# Sheet1.net
KiCad netlist of a schematic drawn in Altium Designer
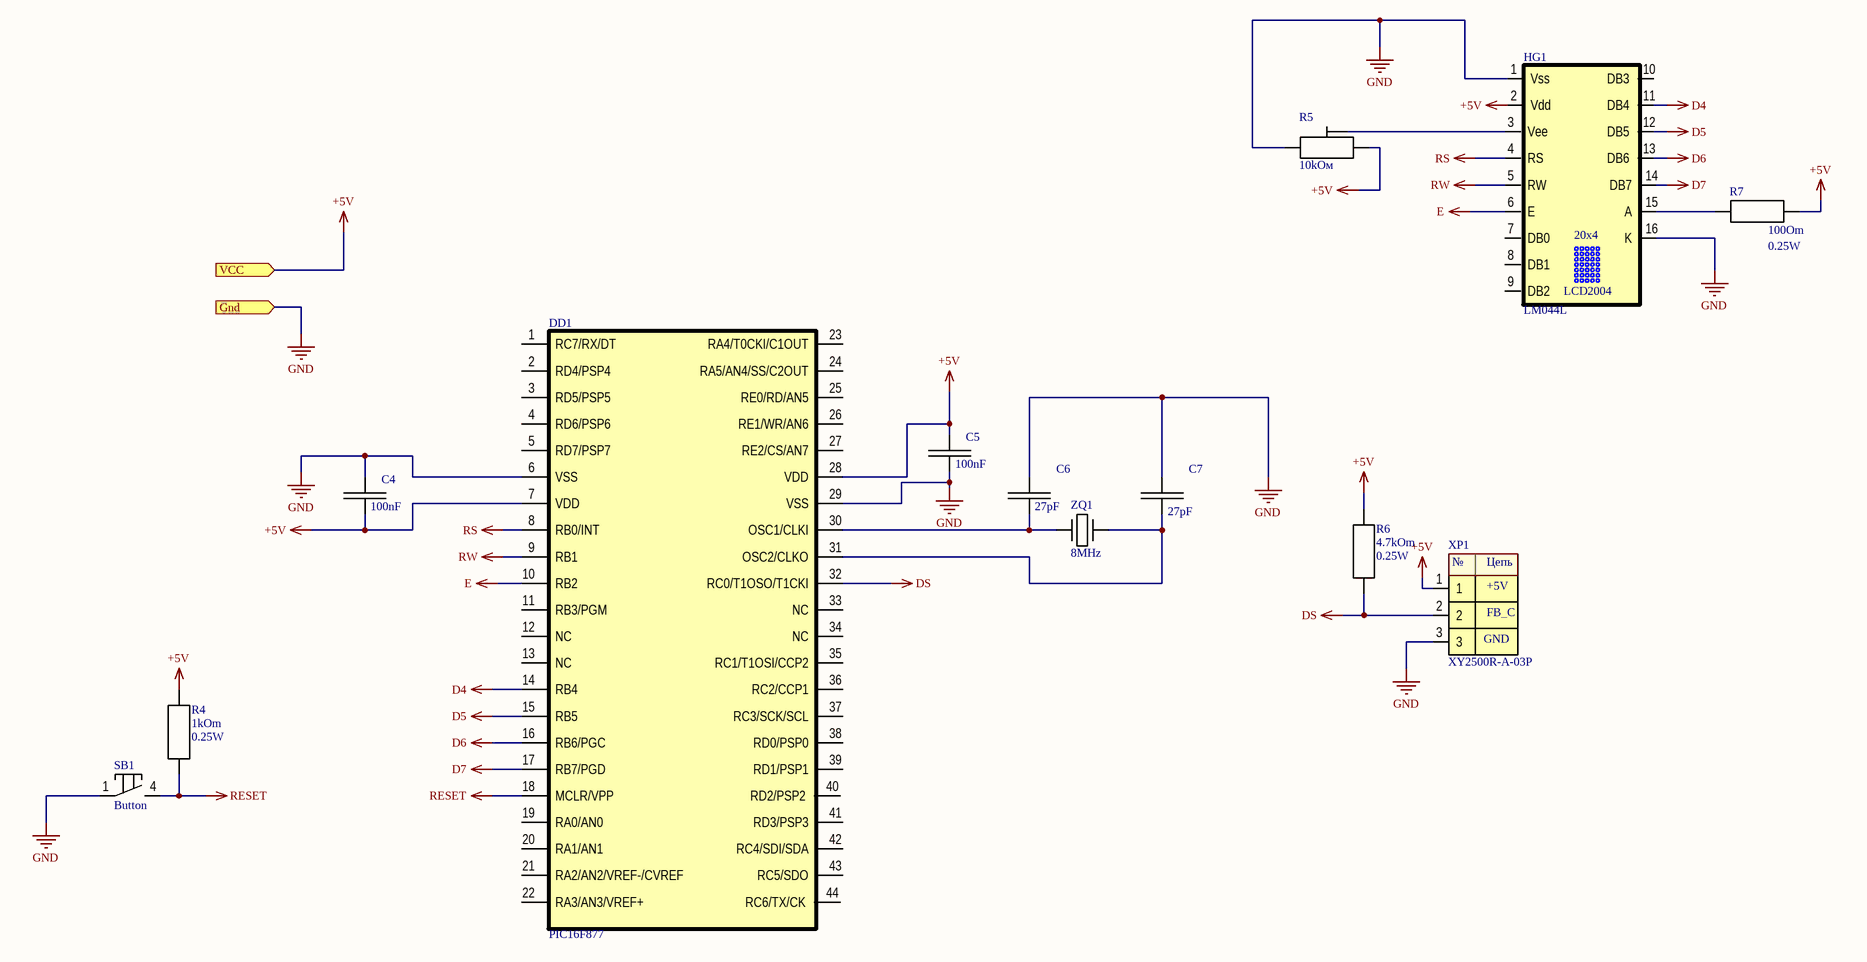
[diagram p0: Sheet1.SchDoc]

(export (version "E")
  (design (tool "Eeschema 10.0.6"))
  (components
    (comp (ref "C4")
      (value "100nF")
      (footprint "CAP1206")
      (fields
        (field (name "VOLTAGE") "100V")
        (field (name "PART NUMBER") "CL31B104KCFNNNE")
        (field (name "MANUFACTURER") "Samsung")
      )
      (libsource (lib "SchlibUGO") (part "Capasitor"))
    )
    (comp (ref "C5")
      (value "100nF")
      (footprint "CAP1206")
      (fields
        (field (name "VOLTAGE") "100V")
        (field (name "PART NUMBER") "CL31B104KCFNNNE")
        (field (name "MANUFACTURER") "Samsung")
      )
      (libsource (lib "SchlibUGO") (part "Capasitor"))
    )
    (comp (ref "C6")
      (value "27pF")
      (footprint "CAP1206")
      (fields
        (field (name "VOLTAGE") "50V")
        (field (name "PART NUMBER") "LFL106270NPO")
        (field (name "MANUFACTURER") "FAITHFULL LINK")
      )
      (libsource (lib "SchlibUGO") (part "Capasitor"))
    )
    (comp (ref "C7")
      (value "27pF")
      (footprint "CAP1206")
      (fields
        (field (name "VOLTAGE") "50V")
        (field (name "PART NUMBER") "FL1206270NPO")
        (field (name "MANUFACTURER") "FAITHFULL LINK")
      )
      (libsource (lib "SchlibUGO") (part "Capasitor"))
    )
    (comp (ref "DD1")
      (value "PIC16F877")
      (footprint "TQFP80P1200X1200X120-44N")
      (fields (field (name "PART NUMBER") "PIC16F877A") (field (name "MANUFACTURER") "Micchip"))
      (libsource (lib "SchlibUGO") (part "PIC16F877"))
    )
    (comp (ref "HG1")
      (value "LM044L")
      (footprint "LCD2004")
      (fields (field (name "PART NUMBER") "LM044L-HD44780U") (field (name "MANUFACTURER") "HITACHI"))
      (libsource (lib "SchlibUGO") (part "LM044L"))
    )
    (comp (ref "R4")
      (value "1kOm")
      (footprint "1206")
      (fields
        (field (name "MANUFACTURER") "Royal Ohm")
        (field (name "PART NUMBER") "SMD1206-1K")
        (field (name "POWER") "0.25W")
        (field (name "Comment") "Resistor")
      )
      (libsource (lib "SchlibUGO") (part "Resistor"))
    )
    (comp (ref "R5")
      (value "10kОм")
      (footprint "3006P")
      (fields
        (field (name "PART NUMBER") "3006-103-Z-LF")
        (field (name "MANUFACTURER") "Bours")
        (field (name "POWER") "0,125W")
      )
      (libsource (lib "SchlibUGO") (part "POT"))
    )
    (comp (ref "R6")
      (value "4.7kOm")
      (footprint "1206")
      (fields
        (field (name "MANUFACTURER") "Royal Ohm")
        (field (name "PART NUMBER") "SMD1206-1K")
        (field (name "POWER") "0.25W")
      )
      (libsource (lib "SchlibUGO") (part "Resistor"))
    )
    (comp (ref "R7")
      (value "100Om")
      (footprint "1206")
      (fields
        (field (name "MANUFACTURER") "YAGEO")
        (field (name "PART NUMBER") "RC1206FR-07100RL")
        (field (name "POWER") "0.25W")
      )
      (libsource (lib "SchlibUGO") (part "Resistor"))
    )
    (comp (ref "SB1") (value "Button") (footprint "KLS2") (libsource (lib "SchlibUGO") (part "Button")))
    (comp (ref "XP1")
      (value "XY2500R-A-03P")
      (footprint "XY2500R-A-03P")
      (fields (field (name "MANUFACTURER") "RUICHI"))
      (libsource (lib "SchlibUGO") (part "XY2500R-A-03P"))
    )
    (comp (ref "ZQ1")
      (value "8MHz")
      (footprint "HC-51U")
      (fields (field (name "PART NUMBER") "HC-51") (field (name "MANUFACTURER") "CHina"))
      (libsource (lib "SchlibUGO") (part "Rzanator"))
    )
  )
  (nets
    (net (code "1") (name "+5V") (class "Default")
      (node (ref "C4") (pin "2") (pinfunction "2_2") (pintype "passive"))
      (node (ref "C5") (pin "1") (pinfunction "1_1") (pintype "passive"))
      (node (ref "DD1") (pin "28") (pinfunction "VDD_28") (pintype "passive"))
      (node (ref "DD1") (pin "7") (pinfunction "VDD_7") (pintype "passive"))
      (node (ref "HG1") (pin "2") (pinfunction "Vdd_2") (pintype "passive"))
      (node (ref "R4") (pin "2") (pinfunction "2_2") (pintype "passive"))
      (node (ref "R5") (pin "3") (pinfunction "3_3") (pintype "passive"))
      (node (ref "R6") (pin "2") (pinfunction "2_2") (pintype "passive"))
      (node (ref "R7") (pin "1") (pinfunction "1_1") (pintype "passive"))
      (node (ref "XP1") (pin "1") (pinfunction "1_1") (pintype "passive"))
    )
    (net (code "2") (name "D4") (class "Default")
      (node (ref "DD1") (pin "14") (pinfunction "RB4_14") (pintype "passive"))
      (node (ref "HG1") (pin "11") (pinfunction "DB4_11") (pintype "passive"))
    )
    (net (code "3") (name "D5") (class "Default")
      (node (ref "DD1") (pin "15") (pinfunction "RB5_15") (pintype "passive"))
      (node (ref "HG1") (pin "12") (pinfunction "DB5_12") (pintype "passive"))
    )
    (net (code "4") (name "D6") (class "Default")
      (node (ref "DD1") (pin "16") (pinfunction "RB6/PGC_16") (pintype "passive"))
      (node (ref "HG1") (pin "13") (pinfunction "DB6_13") (pintype "passive"))
    )
    (net (code "5") (name "D7") (class "Default")
      (node (ref "DD1") (pin "17") (pinfunction "RB7/PGD_17") (pintype "passive"))
      (node (ref "HG1") (pin "14") (pinfunction "DB7_14") (pintype "passive"))
    )
    (net (code "6") (name "DS") (class "Default")
      (node (ref "DD1") (pin "32") (pinfunction "RC0/T1OSO/T1CKI_32") (pintype "passive"))
      (node (ref "R6") (pin "1") (pinfunction "1_1") (pintype "passive"))
      (node (ref "XP1") (pin "2") (pinfunction "2_2") (pintype "passive"))
    )
    (net (code "7") (name "E") (class "Default")
      (node (ref "DD1") (pin "10") (pinfunction "RB2_10") (pintype "passive"))
      (node (ref "HG1") (pin "6") (pinfunction "E_6") (pintype "passive"))
    )
    (net (code "8") (name "GND") (class "Default")
      (node (ref "C4") (pin "1") (pinfunction "1_1") (pintype "passive"))
      (node (ref "C5") (pin "2") (pinfunction "2_2") (pintype "passive"))
      (node (ref "C6") (pin "1") (pinfunction "1_1") (pintype "passive"))
      (node (ref "C7") (pin "1") (pinfunction "1_1") (pintype "passive"))
      (node (ref "DD1") (pin "29") (pinfunction "VSS_29") (pintype "passive"))
      (node (ref "DD1") (pin "6") (pinfunction "VSS_6") (pintype "passive"))
      (node (ref "HG1") (pin "1") (pinfunction "Vss_1") (pintype "passive"))
      (node (ref "HG1") (pin "16") (pinfunction "K_16") (pintype "passive"))
      (node (ref "R5") (pin "1") (pinfunction "1_1") (pintype "passive"))
      (node (ref "SB1") (pin "1") (pinfunction "1_1") (pintype "passive"))
      (node (ref "XP1") (pin "3") (pinfunction "3_3") (pintype "passive"))
    )
    (net (code "9") (name "Net-(DD1-OSC1{slash}CLKI)") (class "Default")
      (node (ref "C6") (pin "2") (pinfunction "2_2") (pintype "passive"))
      (node (ref "DD1") (pin "30") (pinfunction "OSC1/CLKI_30") (pintype "passive"))
      (node (ref "ZQ1") (pin "1") (pinfunction "1_1") (pintype "passive"))
    )
    (net (code "10") (name "Net-(DD1-OSC2{slash}CLKO)") (class "Default")
      (node (ref "C7") (pin "2") (pinfunction "2_2") (pintype "passive"))
      (node (ref "DD1") (pin "31") (pinfunction "OSC2/CLKO_31") (pintype "passive"))
      (node (ref "ZQ1") (pin "2") (pinfunction "2_2") (pintype "passive"))
    )
    (net (code "11") (name "Net-(HG1-A)") (class "Default")
      (node (ref "HG1") (pin "15") (pinfunction "A_15") (pintype "passive"))
      (node (ref "R7") (pin "2") (pinfunction "2_2") (pintype "passive"))
    )
    (net (code "12") (name "Net-(HG1-Vee)") (class "Default")
      (node (ref "HG1") (pin "3") (pinfunction "Vee_3") (pintype "passive"))
      (node (ref "R5") (pin "2") (pinfunction "2_2") (pintype "passive"))
    )
    (net (code "13") (name "RESET") (class "Default")
      (node (ref "DD1") (pin "18") (pinfunction "MCLR/VPP_18") (pintype "passive"))
      (node (ref "R4") (pin "1") (pinfunction "1_1") (pintype "passive"))
      (node (ref "SB1") (pin "4") (pinfunction "4_4") (pintype "passive"))
    )
    (net (code "14") (name "RS") (class "Default")
      (node (ref "DD1") (pin "8") (pinfunction "RB0/INT_8") (pintype "passive"))
      (node (ref "HG1") (pin "4") (pinfunction "RS_4") (pintype "passive"))
    )
    (net (code "15") (name "RW") (class "Default")
      (node (ref "DD1") (pin "9") (pinfunction "RB1_9") (pintype "passive"))
      (node (ref "HG1") (pin "5") (pinfunction "RW_5") (pintype "passive"))
    )
    (net (code "16") (name "unconnected-(DD1-NC-Pad12)") (class "Default")
      (node (ref "DD1") (pin "12") (pinfunction "NC_12") (pintype "passive"))
    )
    (net (code "17") (name "unconnected-(DD1-NC-Pad13)") (class "Default")
      (node (ref "DD1") (pin "13") (pinfunction "NC_13") (pintype "passive"))
    )
    (net (code "18") (name "unconnected-(DD1-NC-Pad33)") (class "Default")
      (node (ref "DD1") (pin "33") (pinfunction "NC_33") (pintype "passive"))
    )
    (net (code "19") (name "unconnected-(DD1-NC-Pad34)") (class "Default")
      (node (ref "DD1") (pin "34") (pinfunction "NC_34") (pintype "passive"))
    )
    (net (code "20") (name "unconnected-(DD1-RA0{slash}AN0-Pad19)") (class "Default")
      (node (ref "DD1") (pin "19") (pinfunction "RA0/AN0_19") (pintype "passive"))
    )
    (net (code "21") (name "unconnected-(DD1-RA1{slash}AN1-Pad20)") (class "Default")
      (node (ref "DD1") (pin "20") (pinfunction "RA1/AN1_20") (pintype "passive"))
    )
    (net (code "22") (name "unconnected-(DD1-RA2{slash}AN2{slash}VREF-{slash}CVREF-Pad21)") (class "Default")
      (node (ref "DD1") (pin "21") (pinfunction "RA2/AN2/VREF-/CVREF_21") (pintype "passive"))
    )
    (net (code "23") (name "unconnected-(DD1-RA3{slash}AN3{slash}VREF+-Pad22)") (class "Default")
      (node (ref "DD1") (pin "22") (pinfunction "RA3/AN3/VREF+_22") (pintype "passive"))
    )
    (net (code "24") (name "unconnected-(DD1-RA4{slash}T0CKI{slash}C1OUT-Pad23)") (class "Default")
      (node (ref "DD1") (pin "23") (pinfunction "RA4/T0CKI/C1OUT_23") (pintype "passive"))
    )
    (net (code "25") (name "unconnected-(DD1-RA5{slash}AN4{slash}SS{slash}C2OUT-Pad24)") (class "Default")
      (node (ref "DD1") (pin "24") (pinfunction "RA5/AN4/SS/C2OUT_24") (pintype "passive"))
    )
    (net (code "26") (name "unconnected-(DD1-RB3{slash}PGM-Pad11)") (class "Default")
      (node (ref "DD1") (pin "11") (pinfunction "RB3/PGM_11") (pintype "passive"))
    )
    (net (code "27") (name "unconnected-(DD1-RC1{slash}T1OSI{slash}CCP2-Pad35)") (class "Default")
      (node (ref "DD1") (pin "35") (pinfunction "RC1/T1OSI/CCP2_35") (pintype "passive"))
    )
    (net (code "28") (name "unconnected-(DD1-RC2{slash}CCP1-Pad36)") (class "Default")
      (node (ref "DD1") (pin "36") (pinfunction "RC2/CCP1_36") (pintype "passive"))
    )
    (net (code "29") (name "unconnected-(DD1-RC3{slash}SCK{slash}SCL-Pad37)") (class "Default")
      (node (ref "DD1") (pin "37") (pinfunction "RC3/SCK/SCL_37") (pintype "passive"))
    )
    (net (code "30") (name "unconnected-(DD1-RC4{slash}SDI{slash}SDA-Pad42)") (class "Default")
      (node (ref "DD1") (pin "42") (pinfunction "RC4/SDI/SDA_42") (pintype "passive"))
    )
    (net (code "31") (name "unconnected-(DD1-RC5{slash}SDO-Pad43)") (class "Default")
      (node (ref "DD1") (pin "43") (pinfunction "RC5/SDO_43") (pintype "passive"))
    )
    (net (code "32") (name "unconnected-(DD1-RC6{slash}TX{slash}CK-Pad44)") (class "Default")
      (node (ref "DD1") (pin "44") (pinfunction "RC6/TX/CK_44") (pintype "passive"))
    )
    (net (code "33") (name "unconnected-(DD1-RC7{slash}RX{slash}DT-Pad1)") (class "Default")
      (node (ref "DD1") (pin "1") (pinfunction "RC7/RX/DT_1") (pintype "passive"))
    )
    (net (code "34") (name "unconnected-(DD1-RD0{slash}PSP0-Pad38)") (class "Default")
      (node (ref "DD1") (pin "38") (pinfunction "RD0/PSP0_38") (pintype "passive"))
    )
    (net (code "35") (name "unconnected-(DD1-RD1{slash}PSP1-Pad39)") (class "Default")
      (node (ref "DD1") (pin "39") (pinfunction "RD1/PSP1_39") (pintype "passive"))
    )
    (net (code "36") (name "unconnected-(DD1-RD2{slash}PSP2-Pad40)") (class "Default")
      (node (ref "DD1") (pin "40") (pinfunction "RD2/PSP2_40") (pintype "passive"))
    )
    (net (code "37") (name "unconnected-(DD1-RD3{slash}PSP3-Pad41)") (class "Default")
      (node (ref "DD1") (pin "41") (pinfunction "RD3/PSP3_41") (pintype "passive"))
    )
    (net (code "38") (name "unconnected-(DD1-RD4{slash}PSP4-Pad2)") (class "Default")
      (node (ref "DD1") (pin "2") (pinfunction "RD4/PSP4_2") (pintype "passive"))
    )
    (net (code "39") (name "unconnected-(DD1-RD5{slash}PSP5-Pad3)") (class "Default")
      (node (ref "DD1") (pin "3") (pinfunction "RD5/PSP5_3") (pintype "passive"))
    )
    (net (code "40") (name "unconnected-(DD1-RD6{slash}PSP6-Pad4)") (class "Default")
      (node (ref "DD1") (pin "4") (pinfunction "RD6/PSP6_4") (pintype "passive"))
    )
    (net (code "41") (name "unconnected-(DD1-RD7{slash}PSP7-Pad5)") (class "Default")
      (node (ref "DD1") (pin "5") (pinfunction "RD7/PSP7_5") (pintype "passive"))
    )
    (net (code "42") (name "unconnected-(DD1-RE0{slash}RD{slash}AN5-Pad25)") (class "Default")
      (node (ref "DD1") (pin "25") (pinfunction "RE0/RD/AN5_25") (pintype "passive"))
    )
    (net (code "43") (name "unconnected-(DD1-RE1{slash}WR{slash}AN6-Pad26)") (class "Default")
      (node (ref "DD1") (pin "26") (pinfunction "RE1/WR/AN6_26") (pintype "passive"))
    )
    (net (code "44") (name "unconnected-(DD1-RE2{slash}CS{slash}AN7-Pad27)") (class "Default")
      (node (ref "DD1") (pin "27") (pinfunction "RE2/CS/AN7_27") (pintype "passive"))
    )
    (net (code "45") (name "unconnected-(HG1-DB0-Pad7)") (class "Default")
      (node (ref "HG1") (pin "7") (pinfunction "DB0_7") (pintype "passive"))
    )
    (net (code "46") (name "unconnected-(HG1-DB1-Pad8)") (class "Default")
      (node (ref "HG1") (pin "8") (pinfunction "DB1_8") (pintype "passive"))
    )
    (net (code "47") (name "unconnected-(HG1-DB2-Pad9)") (class "Default")
      (node (ref "HG1") (pin "9") (pinfunction "DB2_9") (pintype "passive"))
    )
    (net (code "48") (name "unconnected-(HG1-DB3-Pad10)") (class "Default")
      (node (ref "HG1") (pin "10") (pinfunction "DB3_10") (pintype "passive"))
    )
  )
)
